# 15P2D_EDA.net
KiCad netlist of a schematic drawn in EasyEDA Pro
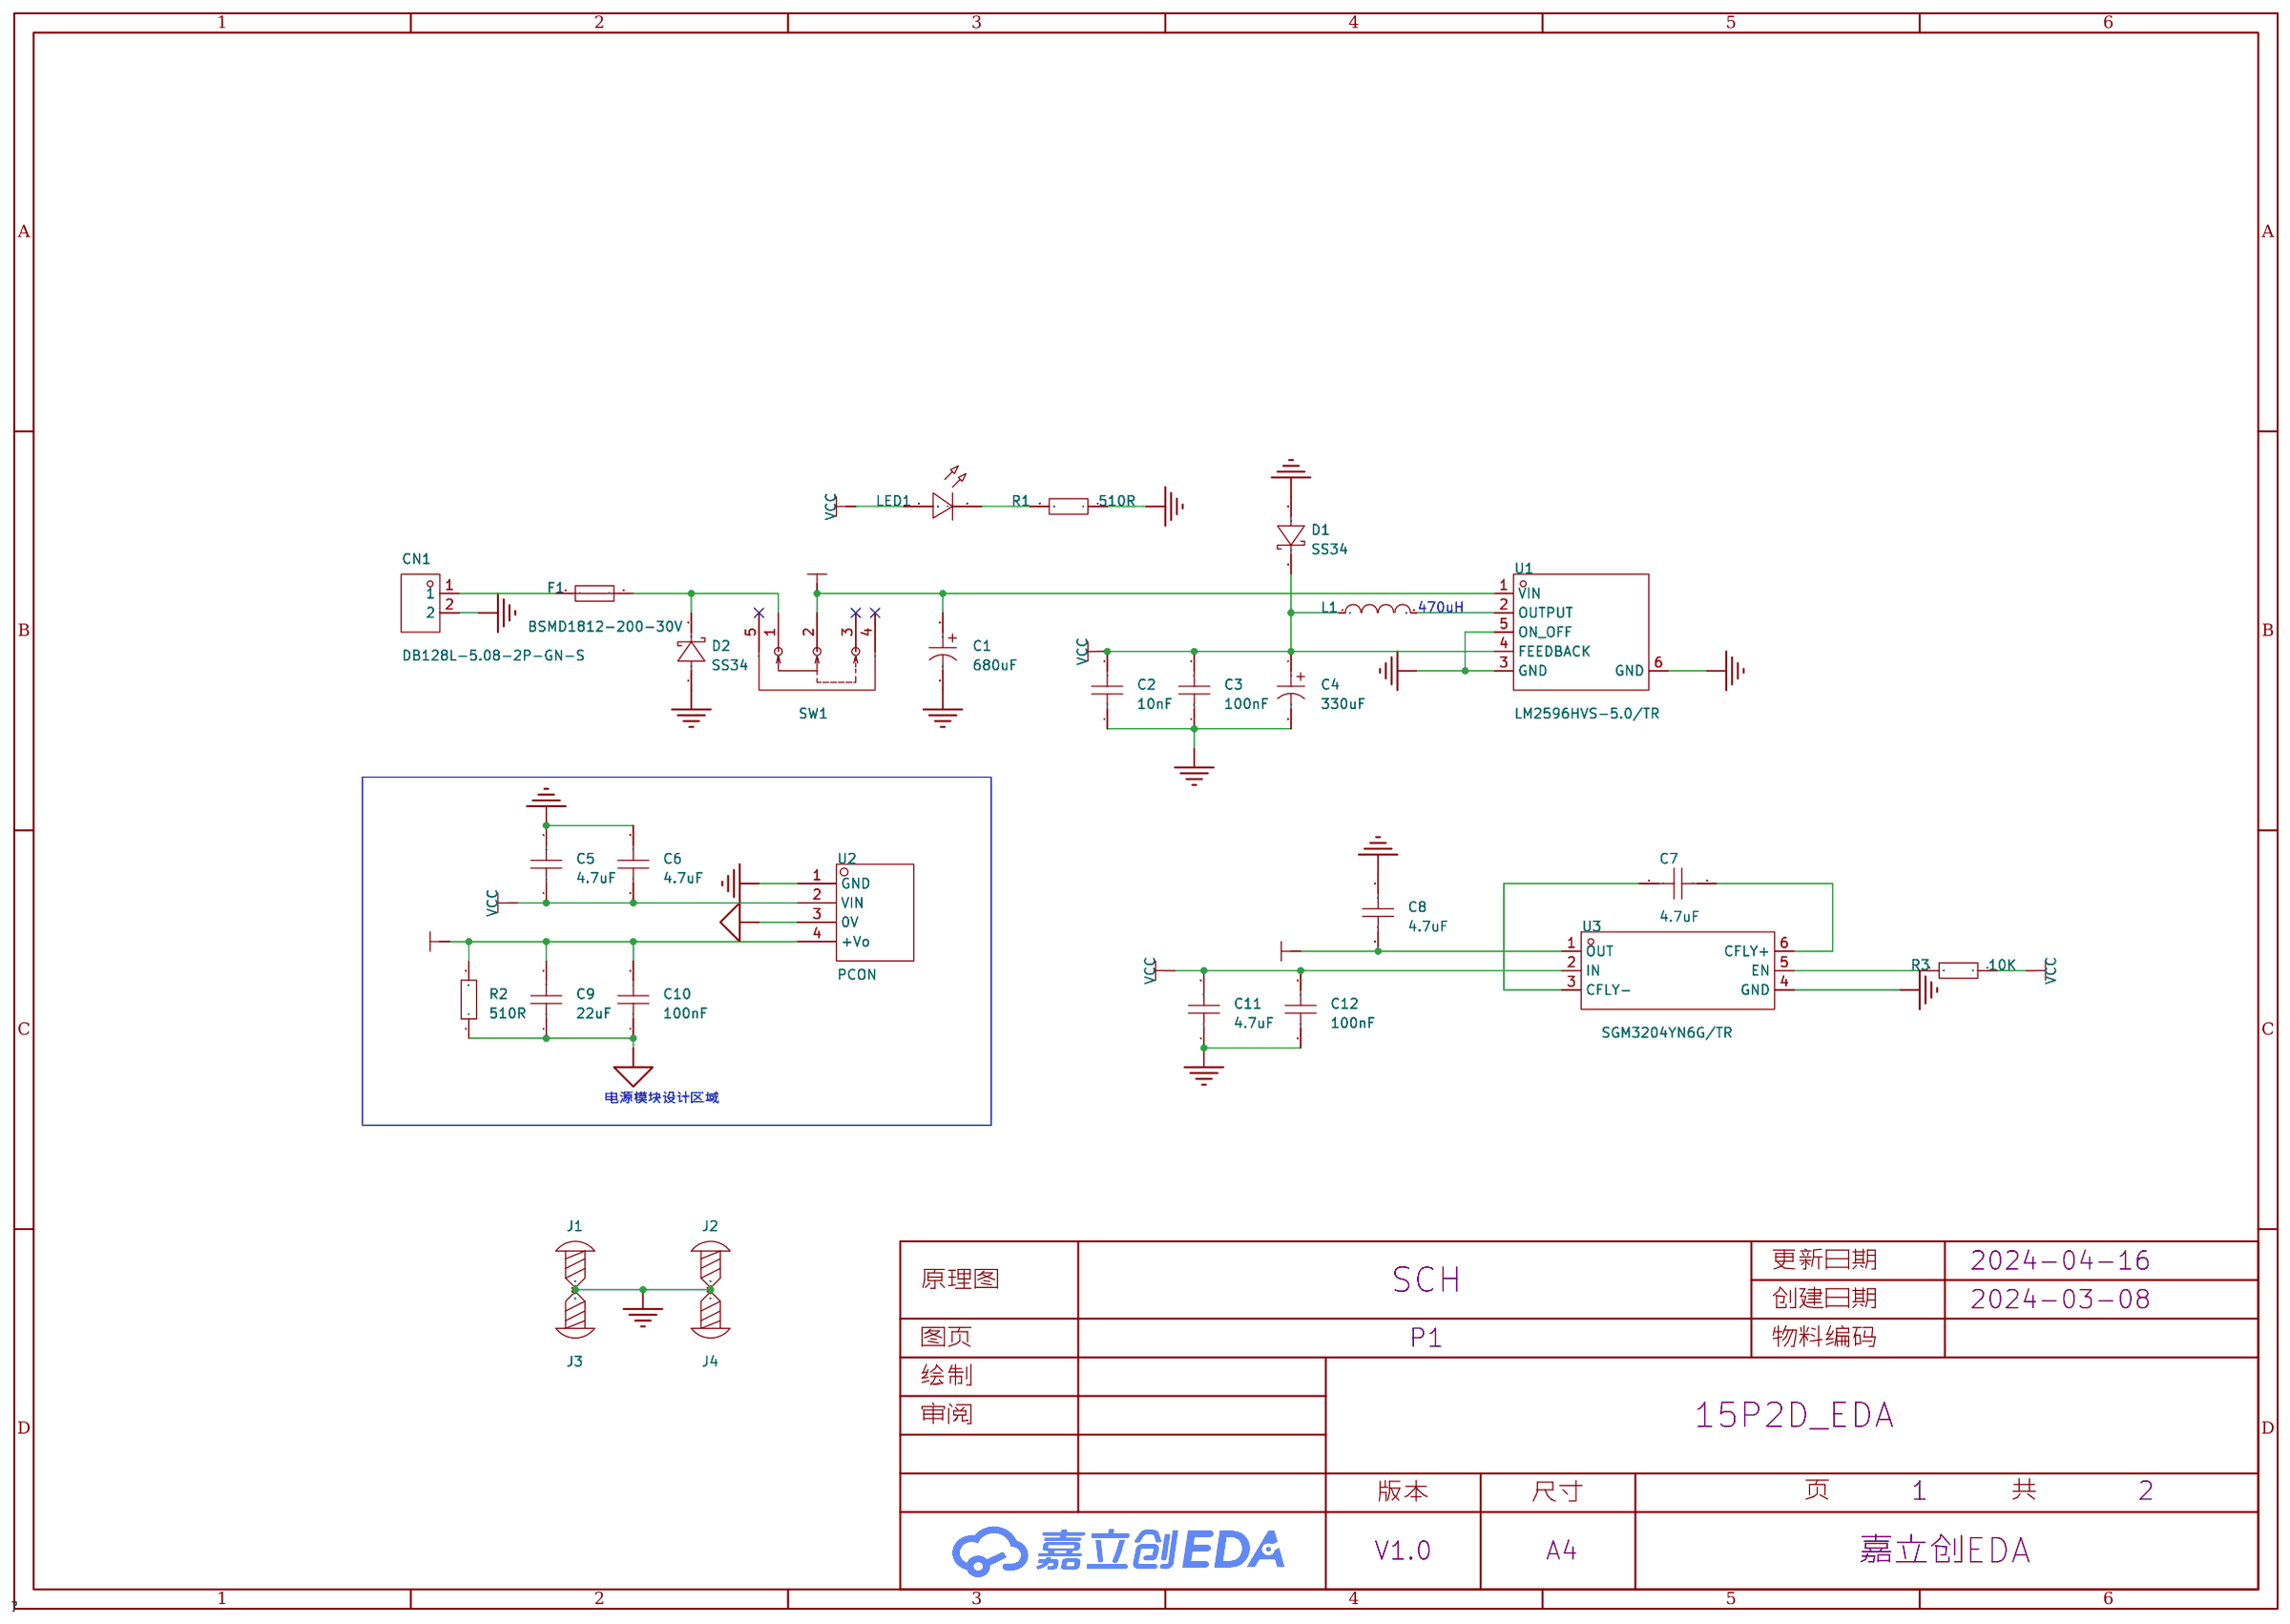
[diagram p0: P1]
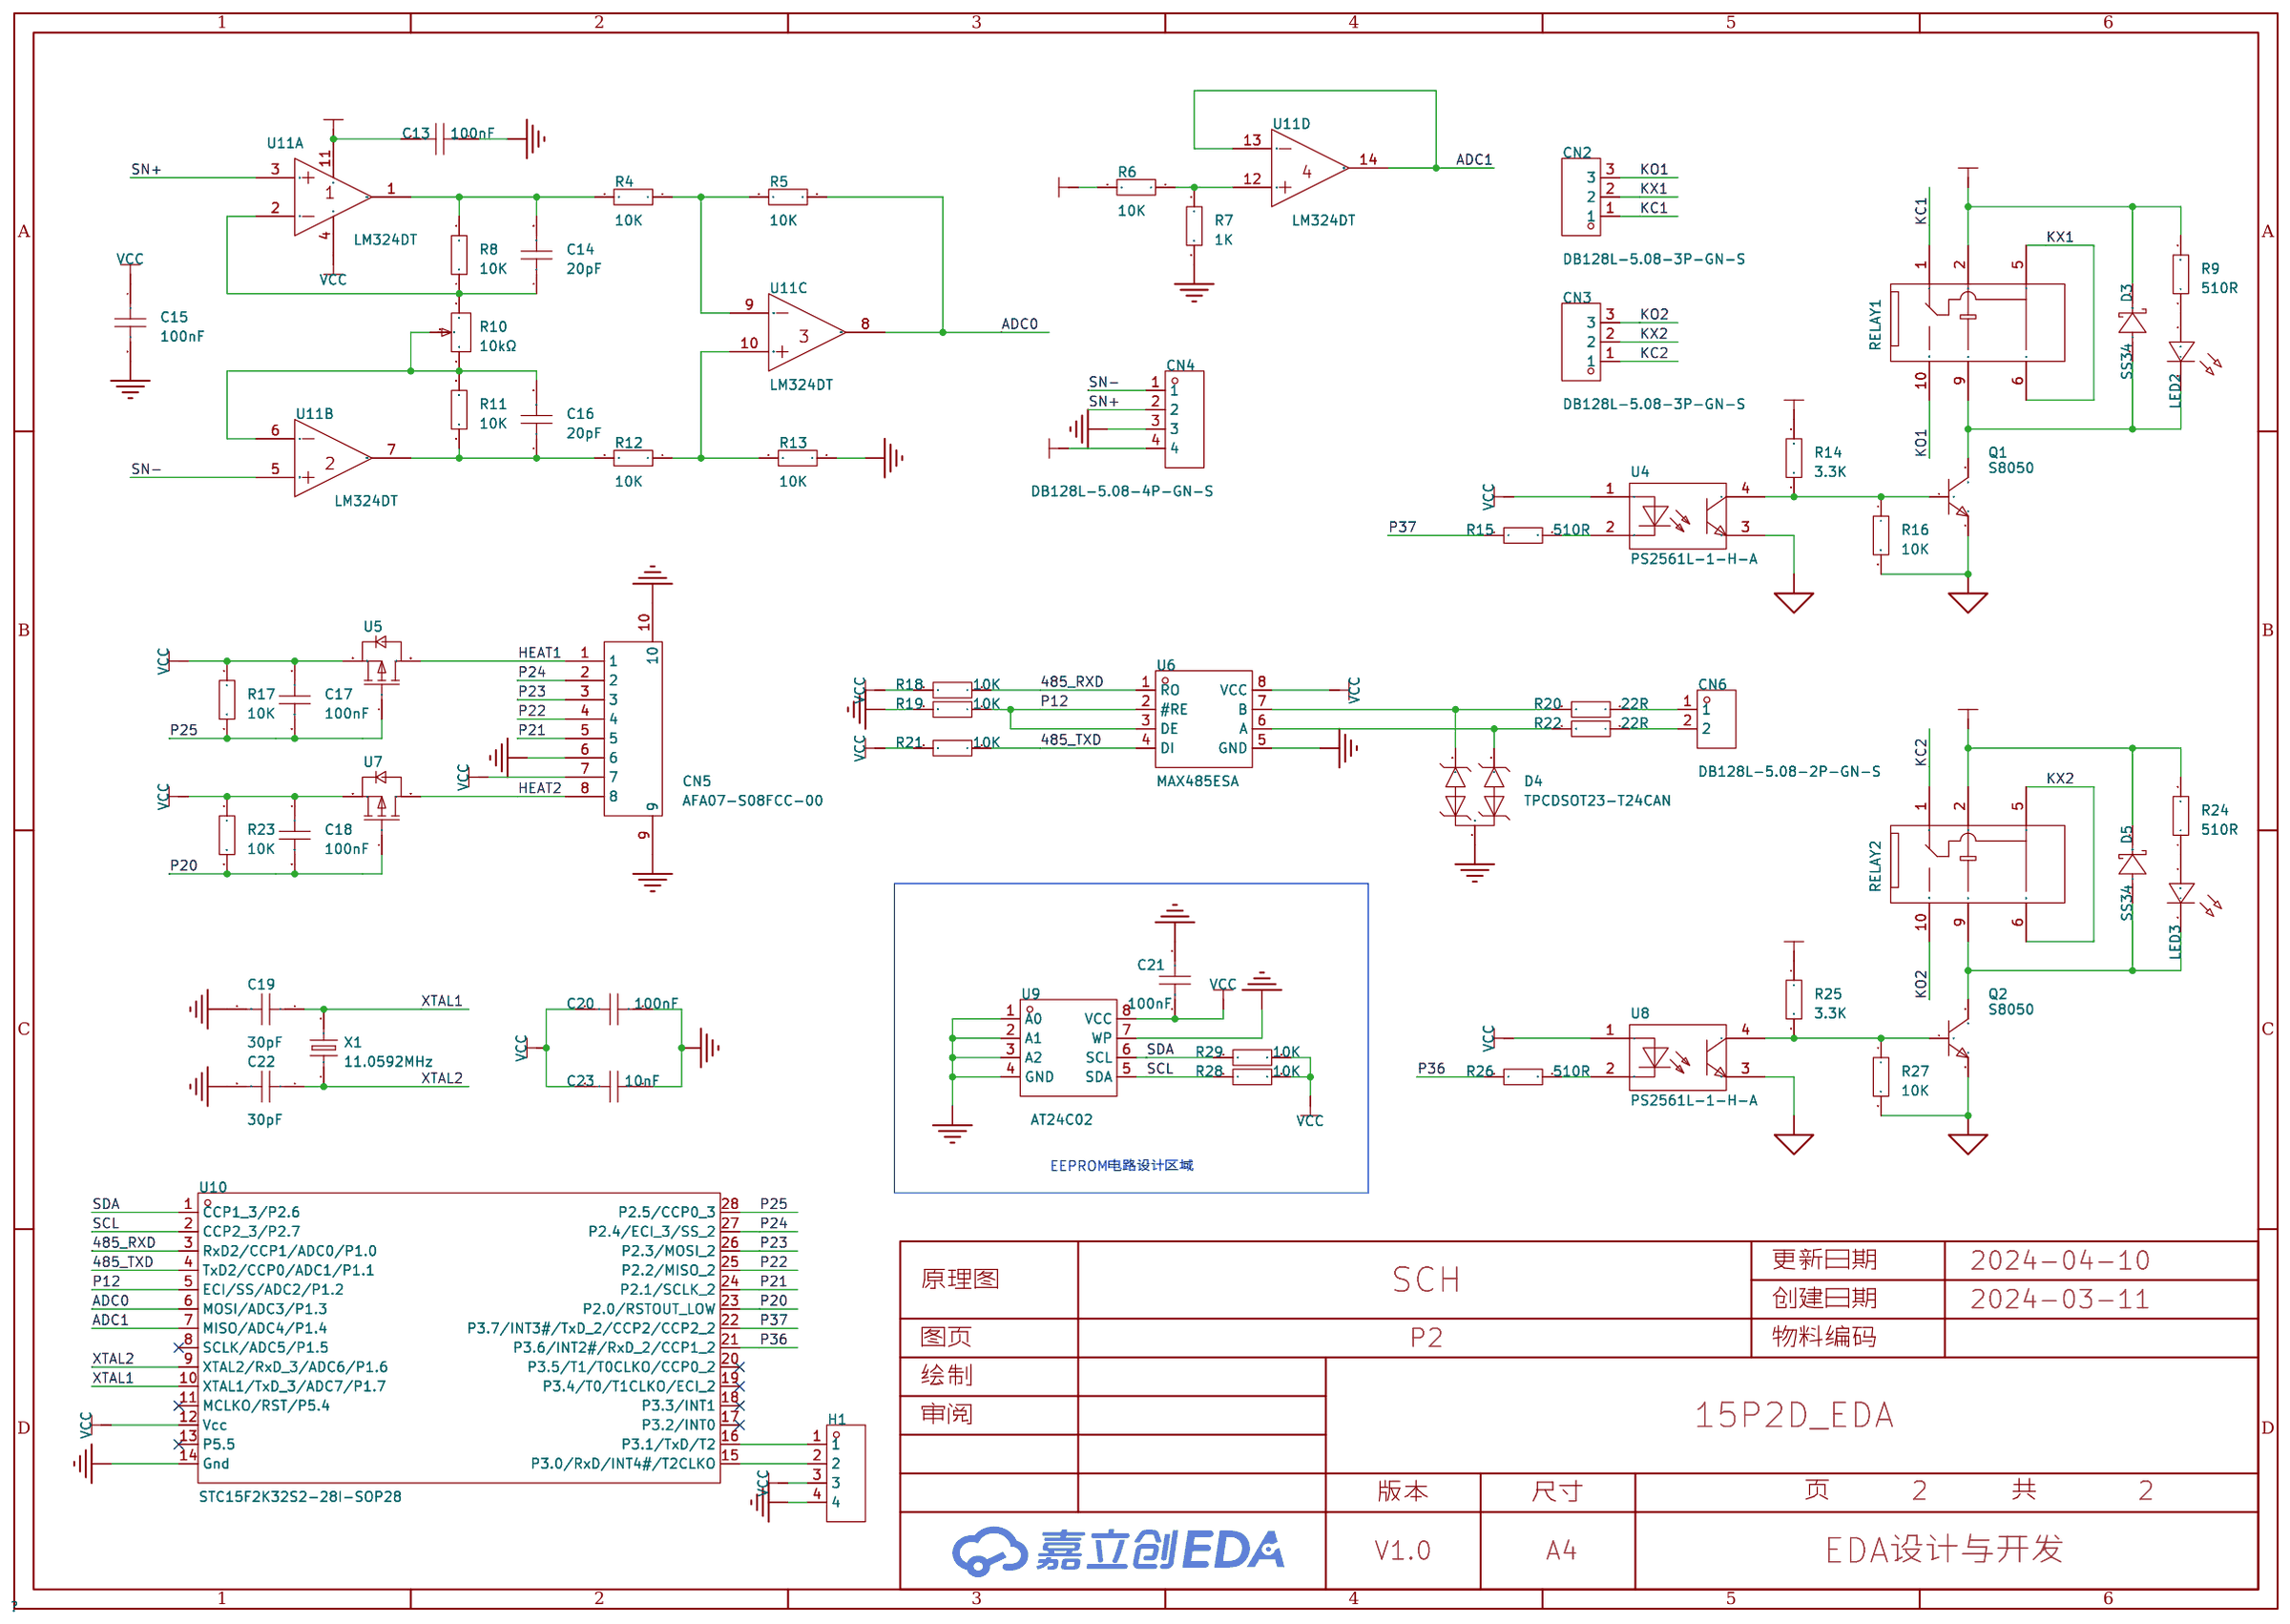
[diagram p1: P2]

(export (version "E")
  (design (tool "Eeschema 10.0.6"))
  (components
    (comp (ref "C1")
      (value "680uF")
      (footprint "easyedapro:CAP-SMD_BD10.0-L10.3-W10.3-LS11.3-FD")
      (description "容值:680uF;精度:±20%;额定电压:35V;纹波电流:380mA;")
      (fields (field (name "Manufacturer Part") "126RV0105") (field (name "Manufacturer") "KNSCHA(科尼盛)"))
      (libsource (lib "easyedapro") (part "126RV0105"))
    )
    (comp (ref "C2")
      (value "10nF")
      (footprint "easyedapro:C0805")
      (libsource (lib "easyedapro") (part "CapAcitance"))
    )
    (comp (ref "C3")
      (value "100nF")
      (footprint "easyedapro:C0805")
      (libsource (lib "easyedapro") (part "CapAcitance"))
    )
    (comp (ref "C4")
      (value "330uF")
      (footprint "easyedapro:CAP-SMD_BD6.3-L6.6-W6.6-LS7.6-RD")
      (description "容值:330uF;精度:±20%;额定电压:16V;纹波电流:170mA;")
      (fields (field (name "Manufacturer Part") "126RV0107") (field (name "Manufacturer") "KNSCHA(科尼盛)"))
      (libsource (lib "easyedapro") (part "126RV0107"))
    )
    (comp (ref "C5")
      (value "4.7uF")
      (footprint "easyedapro:C1206")
      (description "容值:22uF;精度:±10%;额定电压:16V;材质(温度系数):X5R;")
      (fields
        (field (name "Manufacturer Part") "CL31A226KOHNNNE")
        (field (name "Manufacturer") "SAMSUNG(三星)")
      )
      (libsource (lib "easyedapro") (part "CL31A226KOHNNNE"))
    )
    (comp (ref "C6")
      (value "4.7uF")
      (footprint "easyedapro:C1206")
      (description "容值:22uF;精度:±10%;额定电压:16V;材质(温度系数):X5R;")
      (fields
        (field (name "Manufacturer Part") "CL31A226KOHNNNE")
        (field (name "Manufacturer") "SAMSUNG(三星)")
      )
      (libsource (lib "easyedapro") (part "CL31A226KOHNNNE"))
    )
    (comp (ref "C7")
      (value "4.7uF")
      (footprint "easyedapro:C1206")
      (description "容值:22uF;精度:±10%;额定电压:16V;材质(温度系数):X5R;")
      (fields
        (field (name "Manufacturer Part") "CL31A226KOHNNNE")
        (field (name "Manufacturer") "SAMSUNG(三星)")
      )
      (libsource (lib "easyedapro") (part "CL31A226KOHNNNE"))
    )
    (comp (ref "C8")
      (value "4.7uF")
      (footprint "easyedapro:C1206")
      (description "容值:22uF;精度:±10%;额定电压:16V;材质(温度系数):X5R;")
      (fields
        (field (name "Manufacturer Part") "CL31A226KOHNNNE")
        (field (name "Manufacturer") "SAMSUNG(三星)")
      )
      (libsource (lib "easyedapro") (part "CL31A226KOHNNNE"))
    )
    (comp (ref "C9")
      (value "22uF")
      (footprint "easyedapro:C1206")
      (description "容值:22uF;精度:±10%;额定电压:16V;材质(温度系数):X5R;")
      (fields
        (field (name "Manufacturer Part") "CL31A226KOHNNNE")
        (field (name "Manufacturer") "SAMSUNG(三星)")
      )
      (libsource (lib "easyedapro") (part "CL31A226KOHNNNE"))
    )
    (comp (ref "C10")
      (value "100nF")
      (footprint "easyedapro:C0805")
      (libsource (lib "easyedapro") (part "CapAcitance"))
    )
    (comp (ref "C11")
      (value "4.7uF")
      (footprint "easyedapro:C1206")
      (description "容值:22uF;精度:±10%;额定电压:16V;材质(温度系数):X5R;")
      (fields
        (field (name "Manufacturer Part") "CL31A226KOHNNNE")
        (field (name "Manufacturer") "SAMSUNG(三星)")
      )
      (libsource (lib "easyedapro") (part "CL31A226KOHNNNE"))
    )
    (comp (ref "C12")
      (value "100nF")
      (footprint "easyedapro:C0805")
      (libsource (lib "easyedapro") (part "CapAcitance"))
    )
    (comp (ref "CN1")
      (value "DB128L-5.08-2P-GN-S")
      (footprint "easyedapro:CONN-TH_2P-P5.08_DB128L-5.08-2P")
      (fields (field (name "Manufacturer") "DORABO(地博电气)"))
      (libsource (lib "easyedapro") (part "DB128L-5.08-2P"))
    )
    (comp (ref "D1")
      (value "SS34")
      (footprint "easyedapro:SMA_L4.3-W2.5-LS5.0-RD")
      (description "二极管配置:独立式;正向压降(Vf):550mV@3A;直流反向耐压(Vr):40V;平均整流电流(Io):3A;")
      (fields (field (name "Manufacturer") "TWGMC(台湾迪嘉)"))
      (libsource (lib "easyedapro") (part "SS34_C727060"))
    )
    (comp (ref "D2")
      (value "SS34")
      (footprint "easyedapro:SMA_L4.3-W2.5-LS5.0-RD")
      (description "二极管配置:独立式;正向压降(Vf):550mV@3A;直流反向耐压(Vr):40V;平均整流电流(Io):3A;")
      (fields (field (name "Manufacturer") "TWGMC(台湾迪嘉)"))
      (libsource (lib "easyedapro") (part "SS34_C727060"))
    )
    (comp (ref "F1")
      (value "BSMD1812-200-30V")
      (footprint "easyedapro:F1812")
      (description "最大电压:30V;最大电流:40A;保持电流:2A;跳闸电流:4A;")
      (fields (field (name "Manufacturer") "BHFUSE(佰宏)"))
      (libsource (lib "easyedapro") (part "BSMD1812-200-30V"))
    )
    (comp (ref "J1") (value "~") (footprint "easyedapro:M2螺丝") (libsource (lib "easyedapro") (part "螺丝孔")))
    (comp (ref "J2") (value "~") (footprint "easyedapro:M2螺丝") (libsource (lib "easyedapro") (part "螺丝孔")))
    (comp (ref "J3") (value "~") (footprint "easyedapro:M2螺丝") (libsource (lib "easyedapro") (part "螺丝孔")))
    (comp (ref "J4") (value "~") (footprint "easyedapro:M2螺丝") (libsource (lib "easyedapro") (part "螺丝孔")))
    (comp (ref "L1")
      (value "470uH")
      (footprint "easyedapro:IND-SMD_L12.0-W12.0_YPRH120X")
      (description "电感值:470uH;精度:±20%;额定电流:1.06A;")
      (fields (field (name "Manufacturer Part") "YPRH1209-471M") (field (name "Manufacturer") "YJYCOIN(益嘉源)"))
      (libsource (lib "easyedapro") (part "YPRH1209-471M"))
    )
    (comp (ref "LED1")
      (value "~")
      (footprint "easyedapro:LED_TH-3mm")
      (libsource (lib "easyedapro") (part "LED_TH-R"))
    )
    (comp (ref "R1") (value "510R") (footprint "easyedapro:R0805") (libsource (lib "easyedapro") (part "电阻")))
    (comp (ref "R2") (value "510R") (footprint "easyedapro:R0805") (libsource (lib "easyedapro") (part "电阻")))
    (comp (ref "R3") (value "10K") (footprint "easyedapro:R0805") (libsource (lib "easyedapro") (part "电阻")))
    (comp (ref "SW1")
      (value "SK12D07VG4")
      (footprint "easyedapro:SW-TH_SK12D07VG4")
      (description "电路结构:单刀双掷;安装方式:侧插;额定电流(DC):500mA;额定电压(DC):50V;额定电流(AC):-;额定电压(AC):-;机械寿命:5千次;")
      (fields (field (name "Manufacturer") "SHOU HAN(首韩)"))
      (libsource (lib "easyedapro") (part "SK12D07VG4"))
    )
    (comp (ref "U1")
      (value "LM2596HVS-5.0/TR")
      (footprint "easyedapro:TO-263-5_L10.2-W8.9-P1.70-LS15.2-BR")
      (fields (field (name "Manufacturer") "HGSEMI(华冠)"))
      (libsource (lib "easyedapro") (part "LM2596HVS-5.0/TR"))
    )
    (comp (ref "U2") (value "PCON") (libsource (lib "easyedapro") (part "PCON")))
    (comp (ref "U3")
      (value "SGM3204YN6G/TR")
      (footprint "easyedapro:SOT-23-6_L2.9-W1.6-P0.95-LS2.8-BR")
      (description "功能类型:-;输入电压:1.4V~5.5V;输出电压:-5.5V~-1.4V;输出电流(最大值):200mA;")
      (fields (field (name "Manufacturer") "SGMICRO(圣邦微)"))
      (libsource (lib "easyedapro") (part "SGM3204YN6G/TR"))
    )
    (comp (ref "C13")
      (value "100nF")
      (footprint "easyedapro:C0805")
      (libsource (lib "easyedapro") (part "CapAcitance"))
    )
    (comp (ref "C14")
      (value "20pF")
      (footprint "easyedapro:C0805")
      (libsource (lib "easyedapro") (part "CapAcitance"))
    )
    (comp (ref "C15")
      (value "100nF")
      (footprint "easyedapro:C0805")
      (libsource (lib "easyedapro") (part "CapAcitance"))
    )
    (comp (ref "C16")
      (value "20pF")
      (footprint "easyedapro:C0805")
      (libsource (lib "easyedapro") (part "CapAcitance"))
    )
    (comp (ref "C17")
      (value "100nF")
      (footprint "easyedapro:C0805")
      (libsource (lib "easyedapro") (part "CapAcitance"))
    )
    (comp (ref "C18")
      (value "100nF")
      (footprint "easyedapro:C0805")
      (libsource (lib "easyedapro") (part "CapAcitance"))
    )
    (comp (ref "C19")
      (value "30pF")
      (footprint "easyedapro:C0805")
      (libsource (lib "easyedapro") (part "CapAcitance"))
    )
    (comp (ref "C20")
      (value "100nF")
      (footprint "easyedapro:C0805")
      (libsource (lib "easyedapro") (part "CapAcitance"))
    )
    (comp (ref "C21")
      (value "100nF")
      (footprint "easyedapro:C0805")
      (libsource (lib "easyedapro") (part "CapAcitance"))
    )
    (comp (ref "C22")
      (value "30pF")
      (footprint "easyedapro:C0805")
      (libsource (lib "easyedapro") (part "CapAcitance"))
    )
    (comp (ref "C23")
      (value "10nF")
      (footprint "easyedapro:C0805")
      (libsource (lib "easyedapro") (part "CapAcitance"))
    )
    (comp (ref "CN2")
      (value "DB128L-5.08-3P-GN-S")
      (footprint "easyedapro:CONN-TH_DB128L-5.08-3P")
      (fields (field (name "Manufacturer") "DORABO(地博电气)"))
      (libsource (lib "easyedapro") (part "DB128L-5.08-3P"))
    )
    (comp (ref "CN3")
      (value "DB128L-5.08-3P-GN-S")
      (footprint "easyedapro:CONN-TH_DB128L-5.08-3P")
      (fields (field (name "Manufacturer") "DORABO(地博电气)"))
      (libsource (lib "easyedapro") (part "DB128L-5.08-3P"))
    )
    (comp (ref "CN4")
      (value "DB128L-5.08-4P-GN-S")
      (footprint "easyedapro:CONN-TH_4P_DB128L-5.08-4P-GN-S")
      (fields (field (name "Manufacturer") "DORABO(地博电气)"))
      (libsource (lib "easyedapro") (part "DB128L-5.08-4P-GN-S"))
    )
    (comp (ref "CN5")
      (value "AFA07-S08FCC-00")
      (footprint "easyedapro:FPC-SMD_P1.00-8P_LCS-XJ-H2.5")
      (description "锁定特性:抽屉式;触点类型:下接;触点数量:8P;间距:1mm;安装类型:卧贴;")
      (fields (field (name "Manufacturer") "JS(钜硕电子)"))
      (libsource (lib "easyedapro") (part "AFA07-S08FCC-00"))
    )
    (comp (ref "CN6")
      (value "DB128L-5.08-2P-GN-S")
      (footprint "easyedapro:CONN-TH_2P-P5.08_DB128L-5.08-2P")
      (fields (field (name "Manufacturer") "DORABO(地博电气)"))
      (libsource (lib "easyedapro") (part "DB128L-5.08-2P"))
    )
    (comp (ref "D3")
      (value "SS34")
      (footprint "easyedapro:SMA_L4.3-W2.5-LS5.0-RD")
      (description "二极管配置:独立式;正向压降(Vf):550mV@3A;直流反向耐压(Vr):40V;平均整流电流(Io):3A;")
      (fields (field (name "Manufacturer") "TWGMC(台湾迪嘉)"))
      (libsource (lib "easyedapro") (part "SS34_C727060"))
    )
    (comp (ref "D4")
      (value "TPCDSOT23-T24CAN")
      (footprint "easyedapro:SOT-23-3_L2.9-W1.3-P1.90-LS2.4-BR")
      (fields (field (name "Manufacturer") "TECH PUBLIC(台舟)"))
      (libsource (lib "easyedapro") (part "TPCDSOT23-T24CAN"))
    )
    (comp (ref "D5")
      (value "SS34")
      (footprint "easyedapro:SMA_L4.3-W2.5-LS5.0-RD")
      (description "二极管配置:独立式;正向压降(Vf):550mV@3A;直流反向耐压(Vr):40V;平均整流电流(Io):3A;")
      (fields (field (name "Manufacturer") "TWGMC(台湾迪嘉)"))
      (libsource (lib "easyedapro") (part "SS34_C727060"))
    )
    (comp (ref "H1")
      (value "~")
      (footprint "easyedapro:HDR-TH_4P-P2.54-V-F")
      (libsource (lib "easyedapro") (part "2.54-1*4P母"))
    )
    (comp (ref "LED2")
      (value "~")
      (footprint "easyedapro:LED_TH-3mm")
      (libsource (lib "easyedapro") (part "LED_TH-G"))
    )
    (comp (ref "LED3")
      (value "~")
      (footprint "easyedapro:LED_TH-3mm")
      (libsource (lib "easyedapro") (part "LED_TH-G"))
    )
    (comp (ref "Q1")
      (value "S8050")
      (footprint "easyedapro:SOT-23-3_L2.9-W1.3-P1.90-LS2.4-BR")
      (description "晶体管类型:NPN;集电极电流(Ic):500mA;集射极击穿电压(Vceo):25V;功率(Pd):300mW;")
      (fields (field (name "Manufacturer") "YONGYUTAI(永裕泰)"))
      (libsource (lib "easyedapro") (part "S8050_C2891804"))
    )
    (comp (ref "Q2")
      (value "S8050")
      (footprint "easyedapro:SOT-23-3_L2.9-W1.3-P1.90-LS2.4-BR")
      (description "晶体管类型:NPN;集电极电流(Ic):500mA;集射极击穿电压(Vceo):25V;功率(Pd):300mW;")
      (fields (field (name "Manufacturer") "YONGYUTAI(永裕泰)"))
      (libsource (lib "easyedapro") (part "S8050_C2891804"))
    )
    (comp (ref "R4") (value "10K") (footprint "easyedapro:R0805") (libsource (lib "easyedapro") (part "电阻")))
    (comp (ref "R5") (value "10K") (footprint "easyedapro:R0805") (libsource (lib "easyedapro") (part "电阻")))
    (comp (ref "R6") (value "10K") (footprint "easyedapro:R0805") (libsource (lib "easyedapro") (part "电阻")))
    (comp (ref "R7") (value "1K") (footprint "easyedapro:R0805") (libsource (lib "easyedapro") (part "电阻")))
    (comp (ref "R8") (value "10K") (footprint "easyedapro:R0805") (libsource (lib "easyedapro") (part "电阻")))
    (comp (ref "R9") (value "510R") (footprint "easyedapro:R0805") (libsource (lib "easyedapro") (part "电阻")))
    (comp (ref "R10")
      (value "10kΩ")
      (footprint "easyedapro:RES-ADJ-TH_3P-L10.0-W10.0-P2.50-BL-BS")
      (description "阻值:20kΩ;精度:±10%;功率:500mW;温度系数:±100ppm/°C;")
      (fields (field (name "Manufacturer Part") "3296W-1-203LF") (field (name "Manufacturer") "BOURNS"))
      (libsource (lib "easyedapro") (part "3296W-1-203LF"))
    )
    (comp (ref "R11") (value "10K") (footprint "easyedapro:R0805") (libsource (lib "easyedapro") (part "电阻")))
    (comp (ref "R12") (value "10K") (footprint "easyedapro:R0805") (libsource (lib "easyedapro") (part "电阻")))
    (comp (ref "R13") (value "10K") (footprint "easyedapro:R0805") (libsource (lib "easyedapro") (part "电阻")))
    (comp (ref "R14")
      (value "3.3K")
      (footprint "easyedapro:R0805")
      (libsource (lib "easyedapro") (part "电阻"))
    )
    (comp (ref "R15")
      (value "510R")
      (footprint "easyedapro:R0805")
      (libsource (lib "easyedapro") (part "电阻"))
    )
    (comp (ref "R16") (value "10K") (footprint "easyedapro:R0805") (libsource (lib "easyedapro") (part "电阻")))
    (comp (ref "R17") (value "10K") (footprint "easyedapro:R0805") (libsource (lib "easyedapro") (part "电阻")))
    (comp (ref "R18") (value "10K") (footprint "easyedapro:R0805") (libsource (lib "easyedapro") (part "电阻")))
    (comp (ref "R19") (value "10K") (footprint "easyedapro:R0805") (libsource (lib "easyedapro") (part "电阻")))
    (comp (ref "R20") (value "22R") (footprint "easyedapro:R0805") (libsource (lib "easyedapro") (part "电阻")))
    (comp (ref "R21") (value "10K") (footprint "easyedapro:R0805") (libsource (lib "easyedapro") (part "电阻")))
    (comp (ref "R22") (value "22R") (footprint "easyedapro:R0805") (libsource (lib "easyedapro") (part "电阻")))
    (comp (ref "R23") (value "10K") (footprint "easyedapro:R0805") (libsource (lib "easyedapro") (part "电阻")))
    (comp (ref "R24")
      (value "510R")
      (footprint "easyedapro:R0805")
      (libsource (lib "easyedapro") (part "电阻"))
    )
    (comp (ref "R25")
      (value "3.3K")
      (footprint "easyedapro:R0805")
      (libsource (lib "easyedapro") (part "电阻"))
    )
    (comp (ref "R26")
      (value "510R")
      (footprint "easyedapro:R0805")
      (libsource (lib "easyedapro") (part "电阻"))
    )
    (comp (ref "R27") (value "10K") (footprint "easyedapro:R0805") (libsource (lib "easyedapro") (part "电阻")))
    (comp (ref "R28") (value "10K") (footprint "easyedapro:R0805") (libsource (lib "easyedapro") (part "电阻")))
    (comp (ref "R29") (value "10K") (footprint "easyedapro:R0805") (libsource (lib "easyedapro") (part "电阻")))
    (comp (ref "RELAY1")
      (value "G5V-1 DC5")
      (footprint "easyedapro:RELAY-TH_G5V-1")
      (description "线圈电压:5V;触点形式:一组转换:1C(单刀双掷-转换);触点容量(电阻负载):-;最大切换电压:125V@AC；60V@DC;最大切换电流:1A;")
      (fields (field (name "Manufacturer") "OMRON(欧姆龙)"))
      (libsource (lib "easyedapro") (part "G5V-1-5VDC"))
    )
    (comp (ref "RELAY2")
      (value "G5V-1 DC5")
      (footprint "easyedapro:RELAY-TH_G5V-1")
      (description "线圈电压:5V;触点形式:一组转换:1C(单刀双掷-转换);触点容量(电阻负载):-;最大切换电压:125V@AC；60V@DC;最大切换电流:1A;")
      (fields (field (name "Manufacturer") "OMRON(欧姆龙)"))
      (libsource (lib "easyedapro") (part "G5V-1-5VDC"))
    )
    (comp (ref "U4")
      (value "PS2561L-1-H-A")
      (footprint "easyedapro:SOP-4_L6.5-W4.6-P2.54-LS9.6-TL")
      (fields (field (name "Manufacturer") "California Eastern Laboratories"))
      (libsource (lib "easyedapro") (part "PS2561L-1-H-A"))
    )
    (comp (ref "U5")
      (value "SI2301-ZE")
      (footprint "easyedapro:SOT-23-3_L2.9-W1.3-P1.90-LS2.4-BR")
      (fields (field (name "Manufacturer") "HXY MOSFET(华轩阳电子)"))
      (libsource (lib "easyedapro") (part "SI2301-ZE"))
    )
    (comp (ref "U6")
      (value "MAX485ESA")
      (footprint "easyedapro:SOP-8_L5.0-W4.0-P1.27-LS6.0-BL")
      (fields (field (name "Manufacturer") "UMW(友台半导体)"))
      (libsource (lib "easyedapro") (part "MAX485EAS"))
    )
    (comp (ref "U7")
      (value "SI2301-ZE")
      (footprint "easyedapro:SOT-23-3_L2.9-W1.3-P1.90-LS2.4-BR")
      (fields (field (name "Manufacturer") "HXY MOSFET(华轩阳电子)"))
      (libsource (lib "easyedapro") (part "SI2301-ZE"))
    )
    (comp (ref "U8")
      (value "PS2561L-1-H-A")
      (footprint "easyedapro:SOP-4_L6.5-W4.6-P2.54-LS9.6-TL")
      (fields (field (name "Manufacturer") "California Eastern Laboratories"))
      (libsource (lib "easyedapro") (part "PS2561L-1-H-A"))
    )
    (comp (ref "U9")
      (value "AT24C02")
      (footprint "easyedapro:SOP-8_L4.9-W3.9-P1.27-LS6.0-BL")
      (description "接口类型:I2C;存储容量:2Kbit;时钟频率(fc):400kHz~1MHz;")
      (fields (field (name "Manufacturer") "HXY MOSFET(华轩阳电子)"))
      (libsource (lib "easyedapro") (part "AT24C02_C7470930"))
    )
    (comp (ref "U10")
      (value "STC15F2K32S2-28I-SOP28")
      (footprint "easyedapro:SOP-28_L17.9-W7.5-P1.27-LS10.3-BL")
      (fields (field (name "Manufacturer") "STC(宏晶)"))
      (libsource (lib "easyedapro") (part "STC15F2K32S2-28I-SOP28"))
    )
    (comp (ref "U11")
      (value "LM324DT")
      (footprint "easyedapro:SOIC-14_L8.7-W3.9-P1.27-LS6.0-BL")
      (description "放大器数:四路;增益带宽积(GBP):1.3MHz;输入偏置电流(Ib):20nA;压摆率(SR):0.4V/us;带宽(-3db):-;")
      (fields (field (name "Manufacturer") "ST(意法半导体)"))
      (libsource (lib "easyedapro") (part "LM324DT"))
    )
    (comp (ref "X1")
      (value "11.0592MHz")
      (footprint "easyedapro:HC-49US_L11.5-W4.5-P4.88")
      (description "晶振类型:直插晶振;频率:11.0592MHz;常温频差:±30ppm;外接负载电容:20pF;频率稳定度(全温):±30ppm;")
      (fields
        (field (name "Manufacturer Part") "TAXD11.0592M2GLFBET2T")
        (field (name "Manufacturer") "YJX(雅晶鑫)")
      )
      (libsource (lib "easyedapro") (part "HC-49S11.0592MHZ20PF30PPM"))
    )
  )
  (nets
    (net (code "1") (name "0") (class "Default")
      (node (ref "C10") (pin "1") (pinfunction "1_1") (pintype "input"))
      (node (ref "C9") (pin "1") (pinfunction "1_1") (pintype "unspecified"))
      (node (ref "Q1") (pin "2") (pinfunction "E_2") (pintype "unspecified"))
      (node (ref "Q2") (pin "2") (pinfunction "E_2") (pintype "unspecified"))
      (node (ref "R16") (pin "2") (pinfunction "2_2") (pintype "input"))
      (node (ref "R2") (pin "1") (pinfunction "1_1") (pintype "input"))
      (node (ref "R27") (pin "2") (pinfunction "2_2") (pintype "input"))
      (node (ref "U2") (pin "3") (pinfunction "0V_3") (pintype "input"))
      (node (ref "U4") (pin "3") (pinfunction "3_3") (pintype "input"))
      (node (ref "U8") (pin "3") (pinfunction "3_3") (pintype "input"))
    )
    (net (code "2") (name "485_RXD") (class "Default")
      (node (ref "R18") (pin "1") (pinfunction "1_1") (pintype "input"))
      (node (ref "U10") (pin "3") (pinfunction "RxD2/CCP1/ADC0/P1.0_3") (pintype "input"))
      (node (ref "U6") (pin "1") (pinfunction "RO_1") (pintype "unspecified"))
    )
    (net (code "3") (name "485_TXD") (class "Default")
      (node (ref "R21") (pin "1") (pinfunction "1_1") (pintype "input"))
      (node (ref "U10") (pin "4") (pinfunction "TxD2/CCP0/ADC1/P1.1_4") (pintype "input"))
      (node (ref "U6") (pin "4") (pinfunction "DI_4") (pintype "unspecified"))
    )
    (net (code "4") (name "ADC0") (class "Default")
      (node (ref "R5") (pin "1") (pinfunction "1_1") (pintype "input"))
      (node (ref "U10") (pin "6") (pinfunction "MOSI/ADC3/P1.3_6") (pintype "input"))
      (node (ref "U11") (pin "8") (pinfunction "OUT3_8") (pintype "unspecified"))
    )
    (net (code "5") (name "ADC1") (class "Default")
      (node (ref "U10") (pin "7") (pinfunction "MISO/ADC4/P1.4_7") (pintype "input"))
      (node (ref "U11") (pin "13") (pinfunction "IN4-_13") (pintype "unspecified"))
      (node (ref "U11") (pin "14") (pinfunction "OUT4_14") (pintype "unspecified"))
    )
    (net (code "6") (name "GND") (class "Default")
      (node (ref "C1") (pin "2") (pinfunction "2_2") (pintype "input"))
      (node (ref "C11") (pin "1") (pinfunction "1_1") (pintype "unspecified"))
      (node (ref "C12") (pin "1") (pinfunction "1_1") (pintype "input"))
      (node (ref "C13") (pin "1") (pinfunction "1_1") (pintype "input"))
      (node (ref "C15") (pin "2") (pinfunction "2_2") (pintype "input"))
      (node (ref "C19") (pin "2") (pinfunction "2_2") (pintype "input"))
      (node (ref "C2") (pin "1") (pinfunction "1_1") (pintype "input"))
      (node (ref "C20") (pin "1") (pinfunction "1_1") (pintype "input"))
      (node (ref "C21") (pin "2") (pinfunction "2_2") (pintype "input"))
      (node (ref "C22") (pin "2") (pinfunction "2_2") (pintype "input"))
      (node (ref "C23") (pin "1") (pinfunction "1_1") (pintype "input"))
      (node (ref "C3") (pin "1") (pinfunction "1_1") (pintype "input"))
      (node (ref "C4") (pin "2") (pinfunction "2_2") (pintype "input"))
      (node (ref "C5") (pin "2") (pinfunction "2_2") (pintype "unspecified"))
      (node (ref "C6") (pin "2") (pinfunction "2_2") (pintype "unspecified"))
      (node (ref "C8") (pin "1") (pinfunction "1_1") (pintype "unspecified"))
      (node (ref "CN1") (pin "2") (pinfunction "2_2") (pintype "unspecified"))
      (node (ref "CN4") (pin "3") (pinfunction "3_3") (pintype "unspecified"))
      (node (ref "CN5") (pin "10") (pinfunction "10_10") (pintype "unspecified"))
      (node (ref "CN5") (pin "6") (pinfunction "6_6") (pintype "unspecified"))
      (node (ref "CN5") (pin "9") (pinfunction "9_9") (pintype "unspecified"))
      (node (ref "D1") (pin "2") (pinfunction "A_2") (pintype "unspecified"))
      (node (ref "D2") (pin "2") (pinfunction "A_2") (pintype "unspecified"))
      (node (ref "D4") (pin "3") (pinfunction "3_3") (pintype "unspecified"))
      (node (ref "H1") (pin "4") (pinfunction "4_4") (pintype "unspecified"))
      (node (ref "J1") (pin "1") (pinfunction "1_1") (pintype "input"))
      (node (ref "J2") (pin "1") (pinfunction "1_1") (pintype "input"))
      (node (ref "J3") (pin "1") (pinfunction "1_1") (pintype "input"))
      (node (ref "J4") (pin "1") (pinfunction "1_1") (pintype "input"))
      (node (ref "R1") (pin "1") (pinfunction "1_1") (pintype "input"))
      (node (ref "R13") (pin "1") (pinfunction "1_1") (pintype "input"))
      (node (ref "R19") (pin "2") (pinfunction "2_2") (pintype "input"))
      (node (ref "R7") (pin "2") (pinfunction "2_2") (pintype "input"))
      (node (ref "U1") (pin "3") (pinfunction "GND_3") (pintype "input"))
      (node (ref "U1") (pin "5") (pinfunction "ON_OFF_5") (pintype "input"))
      (node (ref "U1") (pin "6") (pinfunction "GND_6") (pintype "input"))
      (node (ref "U10") (pin "14") (pinfunction "Gnd_14") (pintype "input"))
      (node (ref "U2") (pin "1") (pinfunction "GND_1") (pintype "input"))
      (node (ref "U3") (pin "4") (pinfunction "GND_4") (pintype "unspecified"))
      (node (ref "U6") (pin "5") (pinfunction "GND_5") (pintype "unspecified"))
      (node (ref "U9") (pin "1") (pinfunction "A0_1") (pintype "unspecified"))
      (node (ref "U9") (pin "2") (pinfunction "A1_2") (pintype "unspecified"))
      (node (ref "U9") (pin "3") (pinfunction "A2_3") (pintype "unspecified"))
      (node (ref "U9") (pin "4") (pinfunction "GND_4") (pintype "unspecified"))
      (node (ref "U9") (pin "7") (pinfunction "WP_7") (pintype "unspecified"))
    )
    (net (code "7") (name "HEAT1") (class "Default")
      (node (ref "CN5") (pin "1") (pinfunction "1_1") (pintype "unspecified"))
      (node (ref "U5") (pin "3") (pinfunction "D_3") (pintype "unspecified"))
    )
    (net (code "8") (name "HEAT2") (class "Default")
      (node (ref "CN5") (pin "8") (pinfunction "8_8") (pintype "unspecified"))
      (node (ref "U7") (pin "3") (pinfunction "D_3") (pintype "unspecified"))
    )
    (net (code "9") (name "KC1") (class "Default")
      (node (ref "CN2") (pin "1") (pinfunction "1_1") (pintype "unspecified"))
      (node (ref "RELAY1") (pin "1") (pinfunction "1_1") (pintype "input"))
    )
    (net (code "10") (name "KC2") (class "Default")
      (node (ref "CN3") (pin "1") (pinfunction "1_1") (pintype "unspecified"))
      (node (ref "RELAY2") (pin "1") (pinfunction "1_1") (pintype "input"))
    )
    (net (code "11") (name "KO1") (class "Default")
      (node (ref "CN2") (pin "3") (pinfunction "3_3") (pintype "unspecified"))
      (node (ref "RELAY1") (pin "10") (pinfunction "10_10") (pintype "input"))
    )
    (net (code "12") (name "KO2") (class "Default")
      (node (ref "CN3") (pin "3") (pinfunction "3_3") (pintype "unspecified"))
      (node (ref "RELAY2") (pin "10") (pinfunction "10_10") (pintype "input"))
    )
    (net (code "13") (name "KX1") (class "Default")
      (node (ref "CN2") (pin "2") (pinfunction "2_2") (pintype "unspecified"))
      (node (ref "RELAY1") (pin "5") (pinfunction "5_5") (pintype "input"))
      (node (ref "RELAY1") (pin "6") (pinfunction "6_6") (pintype "input"))
    )
    (net (code "14") (name "KX2") (class "Default")
      (node (ref "CN3") (pin "2") (pinfunction "2_2") (pintype "unspecified"))
      (node (ref "RELAY2") (pin "5") (pinfunction "5_5") (pintype "input"))
      (node (ref "RELAY2") (pin "6") (pinfunction "6_6") (pintype "input"))
    )
    (net (code "15") (name "Net-(CN1-Pad1)") (class "Default")
      (node (ref "CN1") (pin "1") (pinfunction "1_1") (pintype "unspecified"))
      (node (ref "F1") (pin "1") (pinfunction "1_1") (pintype "unspecified"))
    )
    (net (code "16") (name "Net-(CN6-Pad1)") (class "Default")
      (node (ref "CN6") (pin "1") (pinfunction "1_1") (pintype "unspecified"))
      (node (ref "R20") (pin "1") (pinfunction "1_1") (pintype "input"))
    )
    (net (code "17") (name "Net-(CN6-Pad2)") (class "Default")
      (node (ref "CN6") (pin "2") (pinfunction "2_2") (pintype "unspecified"))
      (node (ref "R22") (pin "1") (pinfunction "1_1") (pintype "input"))
    )
    (net (code "18") (name "Net-(D2-C)") (class "Default")
      (node (ref "D2") (pin "1") (pinfunction "C_1") (pintype "unspecified"))
      (node (ref "F1") (pin "2") (pinfunction "2_2") (pintype "unspecified"))
      (node (ref "SW1") (pin "1") (pinfunction "1_1") (pintype "unspecified"))
    )
    (net (code "19") (name "Net-(D3-A)") (class "Default")
      (node (ref "D3") (pin "2") (pinfunction "A_2") (pintype "unspecified"))
      (node (ref "LED2") (pin "2") (pinfunction "A_2") (pintype "input"))
      (node (ref "Q1") (pin "3") (pinfunction "C_3") (pintype "unspecified"))
      (node (ref "RELAY1") (pin "9") (pinfunction "9_9") (pintype "input"))
    )
    (net (code "20") (name "Net-(D5-A)") (class "Default")
      (node (ref "D5") (pin "2") (pinfunction "A_2") (pintype "unspecified"))
      (node (ref "LED3") (pin "2") (pinfunction "A_2") (pintype "input"))
      (node (ref "Q2") (pin "3") (pinfunction "C_3") (pintype "unspecified"))
      (node (ref "RELAY2") (pin "9") (pinfunction "9_9") (pintype "input"))
    )
    (net (code "21") (name "Net-(LED1-A)") (class "Default")
      (node (ref "LED1") (pin "2") (pinfunction "A_2") (pintype "input"))
      (node (ref "R1") (pin "2") (pinfunction "2_2") (pintype "input"))
    )
    (net (code "22") (name "Net-(LED2-C)") (class "Default")
      (node (ref "LED2") (pin "1") (pinfunction "C_1") (pintype "input"))
      (node (ref "R9") (pin "1") (pinfunction "1_1") (pintype "input"))
    )
    (net (code "23") (name "Net-(LED3-C)") (class "Default")
      (node (ref "LED3") (pin "1") (pinfunction "C_1") (pintype "input"))
      (node (ref "R24") (pin "1") (pinfunction "1_1") (pintype "input"))
    )
    (net (code "24") (name "Net-(Q1-B)") (class "Default")
      (node (ref "Q1") (pin "1") (pinfunction "B_1") (pintype "unspecified"))
      (node (ref "R14") (pin "2") (pinfunction "2_2") (pintype "input"))
      (node (ref "R16") (pin "1") (pinfunction "1_1") (pintype "input"))
      (node (ref "U4") (pin "4") (pinfunction "4_4") (pintype "input"))
    )
    (net (code "25") (name "Net-(Q2-B)") (class "Default")
      (node (ref "Q2") (pin "1") (pinfunction "B_1") (pintype "unspecified"))
      (node (ref "R25") (pin "2") (pinfunction "2_2") (pintype "input"))
      (node (ref "R27") (pin "1") (pinfunction "1_1") (pintype "input"))
      (node (ref "U8") (pin "4") (pinfunction "4_4") (pintype "input"))
    )
    (net (code "26") (name "Net-(R15-Pad2)") (class "Default")
      (node (ref "R15") (pin "2") (pinfunction "2_2") (pintype "input"))
      (node (ref "U4") (pin "2") (pinfunction "2_2") (pintype "input"))
    )
    (net (code "27") (name "Net-(R26-Pad2)") (class "Default")
      (node (ref "R26") (pin "2") (pinfunction "2_2") (pintype "input"))
      (node (ref "U8") (pin "2") (pinfunction "2_2") (pintype "input"))
    )
    (net (code "28") (name "Net-(U1-OUTPUT)") (class "Default")
      (node (ref "L1") (pin "2") (pinfunction "2_2") (pintype "unspecified"))
      (node (ref "U1") (pin "2") (pinfunction "OUTPUT_2") (pintype "input"))
    )
    (net (code "29") (name "Net-(U3-CFLY+)") (class "Default")
      (node (ref "C7") (pin "2") (pinfunction "2_2") (pintype "unspecified"))
      (node (ref "U3") (pin "6") (pinfunction "CFLY+_6") (pintype "unspecified"))
    )
    (net (code "30") (name "Net-(U3-CFLY-)") (class "Default")
      (node (ref "C7") (pin "1") (pinfunction "1_1") (pintype "unspecified"))
      (node (ref "U3") (pin "3") (pinfunction "CFLY-_3") (pintype "unspecified"))
    )
    (net (code "31") (name "Net-(U3-EN)") (class "Default")
      (node (ref "R3") (pin "2") (pinfunction "2_2") (pintype "input"))
      (node (ref "U3") (pin "5") (pinfunction "EN_5") (pintype "unspecified"))
    )
    (net (code "32") (name "Net-(U6-A)") (class "Default")
      (node (ref "D4") (pin "1") (pinfunction "1_1") (pintype "unspecified"))
      (node (ref "R22") (pin "2") (pinfunction "2_2") (pintype "input"))
      (node (ref "U6") (pin "6") (pinfunction "A_6") (pintype "unspecified"))
    )
    (net (code "33") (name "Net-(U6-B)") (class "Default")
      (node (ref "D4") (pin "2") (pinfunction "2_2") (pintype "unspecified"))
      (node (ref "R20") (pin "2") (pinfunction "2_2") (pintype "input"))
      (node (ref "U6") (pin "7") (pinfunction "B_7") (pintype "unspecified"))
    )
    (net (code "34") (name "Net-(U10-P3.0{slash}RxD{slash}INT4#{slash}T2CLKO)") (class "Default")
      (node (ref "H1") (pin "2") (pinfunction "2_2") (pintype "unspecified"))
      (node (ref "U10") (pin "15") (pinfunction "P3.0/RxD/INT4#/T2CLKO_15") (pintype "input"))
    )
    (net (code "35") (name "Net-(U10-P3.1{slash}TxD{slash}T2)") (class "Default")
      (node (ref "H1") (pin "1") (pinfunction "1_1") (pintype "unspecified"))
      (node (ref "U10") (pin "16") (pinfunction "P3.1/TxD/T2_16") (pintype "input"))
    )
    (net (code "36") (name "Net-(U11A-IN1-)") (class "Default")
      (node (ref "C14") (pin "1") (pinfunction "1_1") (pintype "input"))
      (node (ref "R10") (pin "1") (pinfunction "1_1") (pintype "input"))
      (node (ref "R8") (pin "1") (pinfunction "1_1") (pintype "input"))
      (node (ref "U11") (pin "2") (pinfunction "IN1-_2") (pintype "unspecified"))
    )
    (net (code "37") (name "Net-(U11A-OUT1)") (class "Default")
      (node (ref "C14") (pin "2") (pinfunction "2_2") (pintype "input"))
      (node (ref "R4") (pin "2") (pinfunction "2_2") (pintype "input"))
      (node (ref "R8") (pin "2") (pinfunction "2_2") (pintype "input"))
      (node (ref "U11") (pin "1") (pinfunction "OUT1_1") (pintype "unspecified"))
    )
    (net (code "38") (name "Net-(U11B-IN2-)") (class "Default")
      (node (ref "C16") (pin "2") (pinfunction "2_2") (pintype "input"))
      (node (ref "R10") (pin "2") (pinfunction "2_2") (pintype "input"))
      (node (ref "R10") (pin "3") (pinfunction "3_3") (pintype "input"))
      (node (ref "R11") (pin "2") (pinfunction "2_2") (pintype "input"))
      (node (ref "U11") (pin "6") (pinfunction "IN2-_6") (pintype "unspecified"))
    )
    (net (code "39") (name "Net-(U11B-OUT2)") (class "Default")
      (node (ref "C16") (pin "1") (pinfunction "1_1") (pintype "input"))
      (node (ref "R11") (pin "1") (pinfunction "1_1") (pintype "input"))
      (node (ref "R12") (pin "2") (pinfunction "2_2") (pintype "input"))
      (node (ref "U11") (pin "7") (pinfunction "OUT2_7") (pintype "unspecified"))
    )
    (net (code "40") (name "Net-(U11C-IN3+)") (class "Default")
      (node (ref "R12") (pin "1") (pinfunction "1_1") (pintype "input"))
      (node (ref "R13") (pin "2") (pinfunction "2_2") (pintype "input"))
      (node (ref "U11") (pin "10") (pinfunction "IN3+_10") (pintype "unspecified"))
    )
    (net (code "41") (name "Net-(U11C-IN3-)") (class "Default")
      (node (ref "R4") (pin "1") (pinfunction "1_1") (pintype "input"))
      (node (ref "R5") (pin "2") (pinfunction "2_2") (pintype "input"))
      (node (ref "U11") (pin "9") (pinfunction "IN3-_9") (pintype "unspecified"))
    )
    (net (code "42") (name "Net-(U11D-IN4+)") (class "Default")
      (node (ref "R6") (pin "1") (pinfunction "1_1") (pintype "input"))
      (node (ref "R7") (pin "1") (pinfunction "1_1") (pintype "input"))
      (node (ref "U11") (pin "12") (pinfunction "IN4+_12") (pintype "unspecified"))
    )
    (net (code "43") (name "P12") (class "Default")
      (node (ref "R19") (pin "1") (pinfunction "1_1") (pintype "input"))
      (node (ref "U10") (pin "5") (pinfunction "ECI/SS/ADC2/P1.2_5") (pintype "input"))
      (node (ref "U6") (pin "2") (pinfunction "#RE_2") (pintype "unspecified"))
      (node (ref "U6") (pin "3") (pinfunction "DE_3") (pintype "unspecified"))
    )
    (net (code "44") (name "P20") (class "Default")
      (node (ref "C18") (pin "2") (pinfunction "2_2") (pintype "input"))
      (node (ref "R23") (pin "2") (pinfunction "2_2") (pintype "input"))
      (node (ref "U10") (pin "23") (pinfunction "P2.0/RSTOUT_LOW_23") (pintype "input"))
      (node (ref "U7") (pin "1") (pinfunction "G_1") (pintype "unspecified"))
    )
    (net (code "45") (name "P21") (class "Default")
      (node (ref "CN5") (pin "5") (pinfunction "5_5") (pintype "unspecified"))
      (node (ref "U10") (pin "24") (pinfunction "P2.1/SCLK_2_24") (pintype "input"))
    )
    (net (code "46") (name "P22") (class "Default")
      (node (ref "CN5") (pin "4") (pinfunction "4_4") (pintype "unspecified"))
      (node (ref "U10") (pin "25") (pinfunction "P2.2/MISO_2_25") (pintype "input"))
    )
    (net (code "47") (name "P23") (class "Default")
      (node (ref "CN5") (pin "3") (pinfunction "3_3") (pintype "unspecified"))
      (node (ref "U10") (pin "26") (pinfunction "P2.3/MOSI_2_26") (pintype "input"))
    )
    (net (code "48") (name "P24") (class "Default")
      (node (ref "CN5") (pin "2") (pinfunction "2_2") (pintype "unspecified"))
      (node (ref "U10") (pin "27") (pinfunction "P2.4/ECI_3/SS_2_27") (pintype "input"))
    )
    (net (code "49") (name "P25") (class "Default")
      (node (ref "C17") (pin "2") (pinfunction "2_2") (pintype "input"))
      (node (ref "R17") (pin "2") (pinfunction "2_2") (pintype "input"))
      (node (ref "U10") (pin "28") (pinfunction "P2.5/CCP0_3_28") (pintype "input"))
      (node (ref "U5") (pin "1") (pinfunction "G_1") (pintype "unspecified"))
    )
    (net (code "50") (name "P36") (class "Default")
      (node (ref "R26") (pin "1") (pinfunction "1_1") (pintype "input"))
      (node (ref "U10") (pin "21") (pinfunction "P3.6/INT2#/RxD_2/CCP1_2_21") (pintype "input"))
    )
    (net (code "51") (name "P37") (class "Default")
      (node (ref "R15") (pin "1") (pinfunction "1_1") (pintype "input"))
      (node (ref "U10") (pin "22") (pinfunction "P3.7/INT3#/TxD_2/CCP2/CCP2_2_22") (pintype "input"))
    )
    (net (code "52") (name "SCL") (class "Default")
      (node (ref "R28") (pin "1") (pinfunction "1_1") (pintype "input"))
      (node (ref "U10") (pin "2") (pinfunction "CCP2_3/P2.7_2") (pintype "input"))
      (node (ref "U9") (pin "5") (pinfunction "SDA_5") (pintype "unspecified"))
    )
    (net (code "53") (name "SDA") (class "Default")
      (node (ref "R29") (pin "1") (pinfunction "1_1") (pintype "input"))
      (node (ref "U10") (pin "1") (pinfunction "CCP1_3/P2.6_1") (pintype "input"))
      (node (ref "U9") (pin "6") (pinfunction "SCL_6") (pintype "unspecified"))
    )
    (net (code "54") (name "SN+") (class "Default")
      (node (ref "CN4") (pin "2") (pinfunction "2_2") (pintype "unspecified"))
      (node (ref "U11") (pin "3") (pinfunction "IN1+_3") (pintype "unspecified"))
    )
    (net (code "55") (name "SN-") (class "Default")
      (node (ref "CN4") (pin "1") (pinfunction "1_1") (pintype "unspecified"))
      (node (ref "U11") (pin "5") (pinfunction "IN2+_5") (pintype "unspecified"))
    )
    (net (code "56") (name "VBAT") (class "Default")
      (node (ref "C1") (pin "1") (pinfunction "1_1") (pintype "input"))
      (node (ref "CN4") (pin "4") (pinfunction "4_4") (pintype "unspecified"))
      (node (ref "R6") (pin "2") (pinfunction "2_2") (pintype "input"))
      (node (ref "SW1") (pin "2") (pinfunction "2_2") (pintype "unspecified"))
      (node (ref "U1") (pin "1") (pinfunction "VIN_1") (pintype "input"))
    )
    (net (code "57") (name "VCC") (class "Default")
      (node (ref "C11") (pin "2") (pinfunction "2_2") (pintype "unspecified"))
      (node (ref "C12") (pin "2") (pinfunction "2_2") (pintype "input"))
      (node (ref "C15") (pin "1") (pinfunction "1_1") (pintype "input"))
      (node (ref "C17") (pin "1") (pinfunction "1_1") (pintype "input"))
      (node (ref "C18") (pin "1") (pinfunction "1_1") (pintype "input"))
      (node (ref "C2") (pin "2") (pinfunction "2_2") (pintype "input"))
      (node (ref "C20") (pin "2") (pinfunction "2_2") (pintype "input"))
      (node (ref "C21") (pin "1") (pinfunction "1_1") (pintype "input"))
      (node (ref "C23") (pin "2") (pinfunction "2_2") (pintype "input"))
      (node (ref "C3") (pin "2") (pinfunction "2_2") (pintype "input"))
      (node (ref "C4") (pin "1") (pinfunction "1_1") (pintype "input"))
      (node (ref "C5") (pin "1") (pinfunction "1_1") (pintype "unspecified"))
      (node (ref "C6") (pin "1") (pinfunction "1_1") (pintype "unspecified"))
      (node (ref "CN5") (pin "7") (pinfunction "7_7") (pintype "unspecified"))
      (node (ref "D1") (pin "1") (pinfunction "C_1") (pintype "unspecified"))
      (node (ref "H1") (pin "3") (pinfunction "3_3") (pintype "unspecified"))
      (node (ref "L1") (pin "1") (pinfunction "1_1") (pintype "unspecified"))
      (node (ref "LED1") (pin "1") (pinfunction "C_1") (pintype "input"))
      (node (ref "R17") (pin "1") (pinfunction "1_1") (pintype "input"))
      (node (ref "R18") (pin "2") (pinfunction "2_2") (pintype "input"))
      (node (ref "R21") (pin "2") (pinfunction "2_2") (pintype "input"))
      (node (ref "R23") (pin "1") (pinfunction "1_1") (pintype "input"))
      (node (ref "R28") (pin "2") (pinfunction "2_2") (pintype "input"))
      (node (ref "R29") (pin "2") (pinfunction "2_2") (pintype "input"))
      (node (ref "R3") (pin "1") (pinfunction "1_1") (pintype "input"))
      (node (ref "U1") (pin "4") (pinfunction "FEEDBACK_4") (pintype "input"))
      (node (ref "U10") (pin "12") (pinfunction "Vcc_12") (pintype "input"))
      (node (ref "U11") (pin "4") (pinfunction "VCC+_4") (pintype "unspecified"))
      (node (ref "U2") (pin "2") (pinfunction "VIN_2") (pintype "input"))
      (node (ref "U3") (pin "2") (pinfunction "IN_2") (pintype "unspecified"))
      (node (ref "U4") (pin "1") (pinfunction "1_1") (pintype "input"))
      (node (ref "U5") (pin "2") (pinfunction "S_2") (pintype "unspecified"))
      (node (ref "U6") (pin "8") (pinfunction "VCC_8") (pintype "unspecified"))
      (node (ref "U7") (pin "2") (pinfunction "S_2") (pintype "unspecified"))
      (node (ref "U8") (pin "1") (pinfunction "1_1") (pintype "input"))
      (node (ref "U9") (pin "8") (pinfunction "VCC_8") (pintype "unspecified"))
    )
    (net (code "58") (name "VEE") (class "Default")
      (node (ref "C13") (pin "2") (pinfunction "2_2") (pintype "input"))
      (node (ref "C8") (pin "2") (pinfunction "2_2") (pintype "unspecified"))
      (node (ref "U11") (pin "11") (pinfunction "VCC-_11") (pintype "unspecified"))
      (node (ref "U3") (pin "1") (pinfunction "OUT_1") (pintype "unspecified"))
    )
    (net (code "59") (name "VRM") (class "Default")
      (node (ref "C10") (pin "2") (pinfunction "2_2") (pintype "input"))
      (node (ref "C9") (pin "2") (pinfunction "2_2") (pintype "unspecified"))
      (node (ref "D3") (pin "1") (pinfunction "C_1") (pintype "unspecified"))
      (node (ref "D5") (pin "1") (pinfunction "C_1") (pintype "unspecified"))
      (node (ref "R14") (pin "1") (pinfunction "1_1") (pintype "input"))
      (node (ref "R2") (pin "2") (pinfunction "2_2") (pintype "input"))
      (node (ref "R24") (pin "2") (pinfunction "2_2") (pintype "input"))
      (node (ref "R25") (pin "1") (pinfunction "1_1") (pintype "input"))
      (node (ref "R9") (pin "2") (pinfunction "2_2") (pintype "input"))
      (node (ref "RELAY1") (pin "2") (pinfunction "2_2") (pintype "input"))
      (node (ref "RELAY2") (pin "2") (pinfunction "2_2") (pintype "input"))
      (node (ref "U2") (pin "4") (pinfunction "+Vo_4") (pintype "input"))
    )
    (net (code "60") (name "XTAL1") (class "Default")
      (node (ref "C19") (pin "1") (pinfunction "1_1") (pintype "input"))
      (node (ref "U10") (pin "10") (pinfunction "XTAL1/TxD_3/ADC7/P1.7_10") (pintype "input"))
      (node (ref "X1") (pin "2") (pinfunction "2_2") (pintype "unspecified"))
    )
    (net (code "61") (name "XTAL2") (class "Default")
      (node (ref "C22") (pin "1") (pinfunction "1_1") (pintype "input"))
      (node (ref "U10") (pin "9") (pinfunction "XTAL2/RxD_3/ADC6/P1.6_9") (pintype "input"))
      (node (ref "X1") (pin "1") (pinfunction "1_1") (pintype "unspecified"))
    )
    (net (code "62") (name "unconnected-(SW1-Pad3)") (class "Default")
      (node (ref "SW1") (pin "3") (pinfunction "3_3") (pintype "unspecified+no_connect"))
    )
    (net (code "63") (name "unconnected-(SW1-Pad4)") (class "Default")
      (node (ref "SW1") (pin "4") (pinfunction "4_4") (pintype "unspecified+no_connect"))
    )
    (net (code "64") (name "unconnected-(SW1-Pad5)") (class "Default")
      (node (ref "SW1") (pin "5") (pinfunction "5_5") (pintype "unspecified+no_connect"))
    )
    (net (code "65") (name "unconnected-(U10-MCLKO{slash}RST{slash}P5.4-Pad11)") (class "Default")
      (node (ref "U10") (pin "11") (pinfunction "MCLKO/RST/P5.4_11") (pintype "input+no_connect"))
    )
    (net (code "66") (name "unconnected-(U10-P3.2{slash}INT0-Pad17)") (class "Default")
      (node (ref "U10") (pin "17") (pinfunction "P3.2/INT0_17") (pintype "input+no_connect"))
    )
    (net (code "67") (name "unconnected-(U10-P3.3{slash}INT1-Pad18)") (class "Default")
      (node (ref "U10") (pin "18") (pinfunction "P3.3/INT1_18") (pintype "input+no_connect"))
    )
    (net (code "68") (name "unconnected-(U10-P3.4{slash}T0{slash}T1CLKO{slash}ECI_2-Pad19)") (class "Default")
      (node (ref "U10") (pin "19") (pinfunction "P3.4/T0/T1CLKO/ECI_2_19") (pintype "input+no_connect"))
    )
    (net (code "69") (name "unconnected-(U10-P3.5{slash}T1{slash}T0CLKO{slash}CCP0_2-Pad20)") (class "Default")
      (node (ref "U10") (pin "20") (pinfunction "P3.5/T1/T0CLKO/CCP0_2_20") (pintype "input+no_connect"))
    )
    (net (code "70") (name "unconnected-(U10-P5.5-Pad13)") (class "Default")
      (node (ref "U10") (pin "13") (pinfunction "P5.5_13") (pintype "input+no_connect"))
    )
    (net (code "71") (name "unconnected-(U10-SCLK{slash}ADC5{slash}P1.5-Pad8)") (class "Default")
      (node (ref "U10") (pin "8") (pinfunction "SCLK/ADC5/P1.5_8") (pintype "input+no_connect"))
    )
  )
)
